# Schematic.net
KiCad netlist of a schematic drawn in EasyEDA
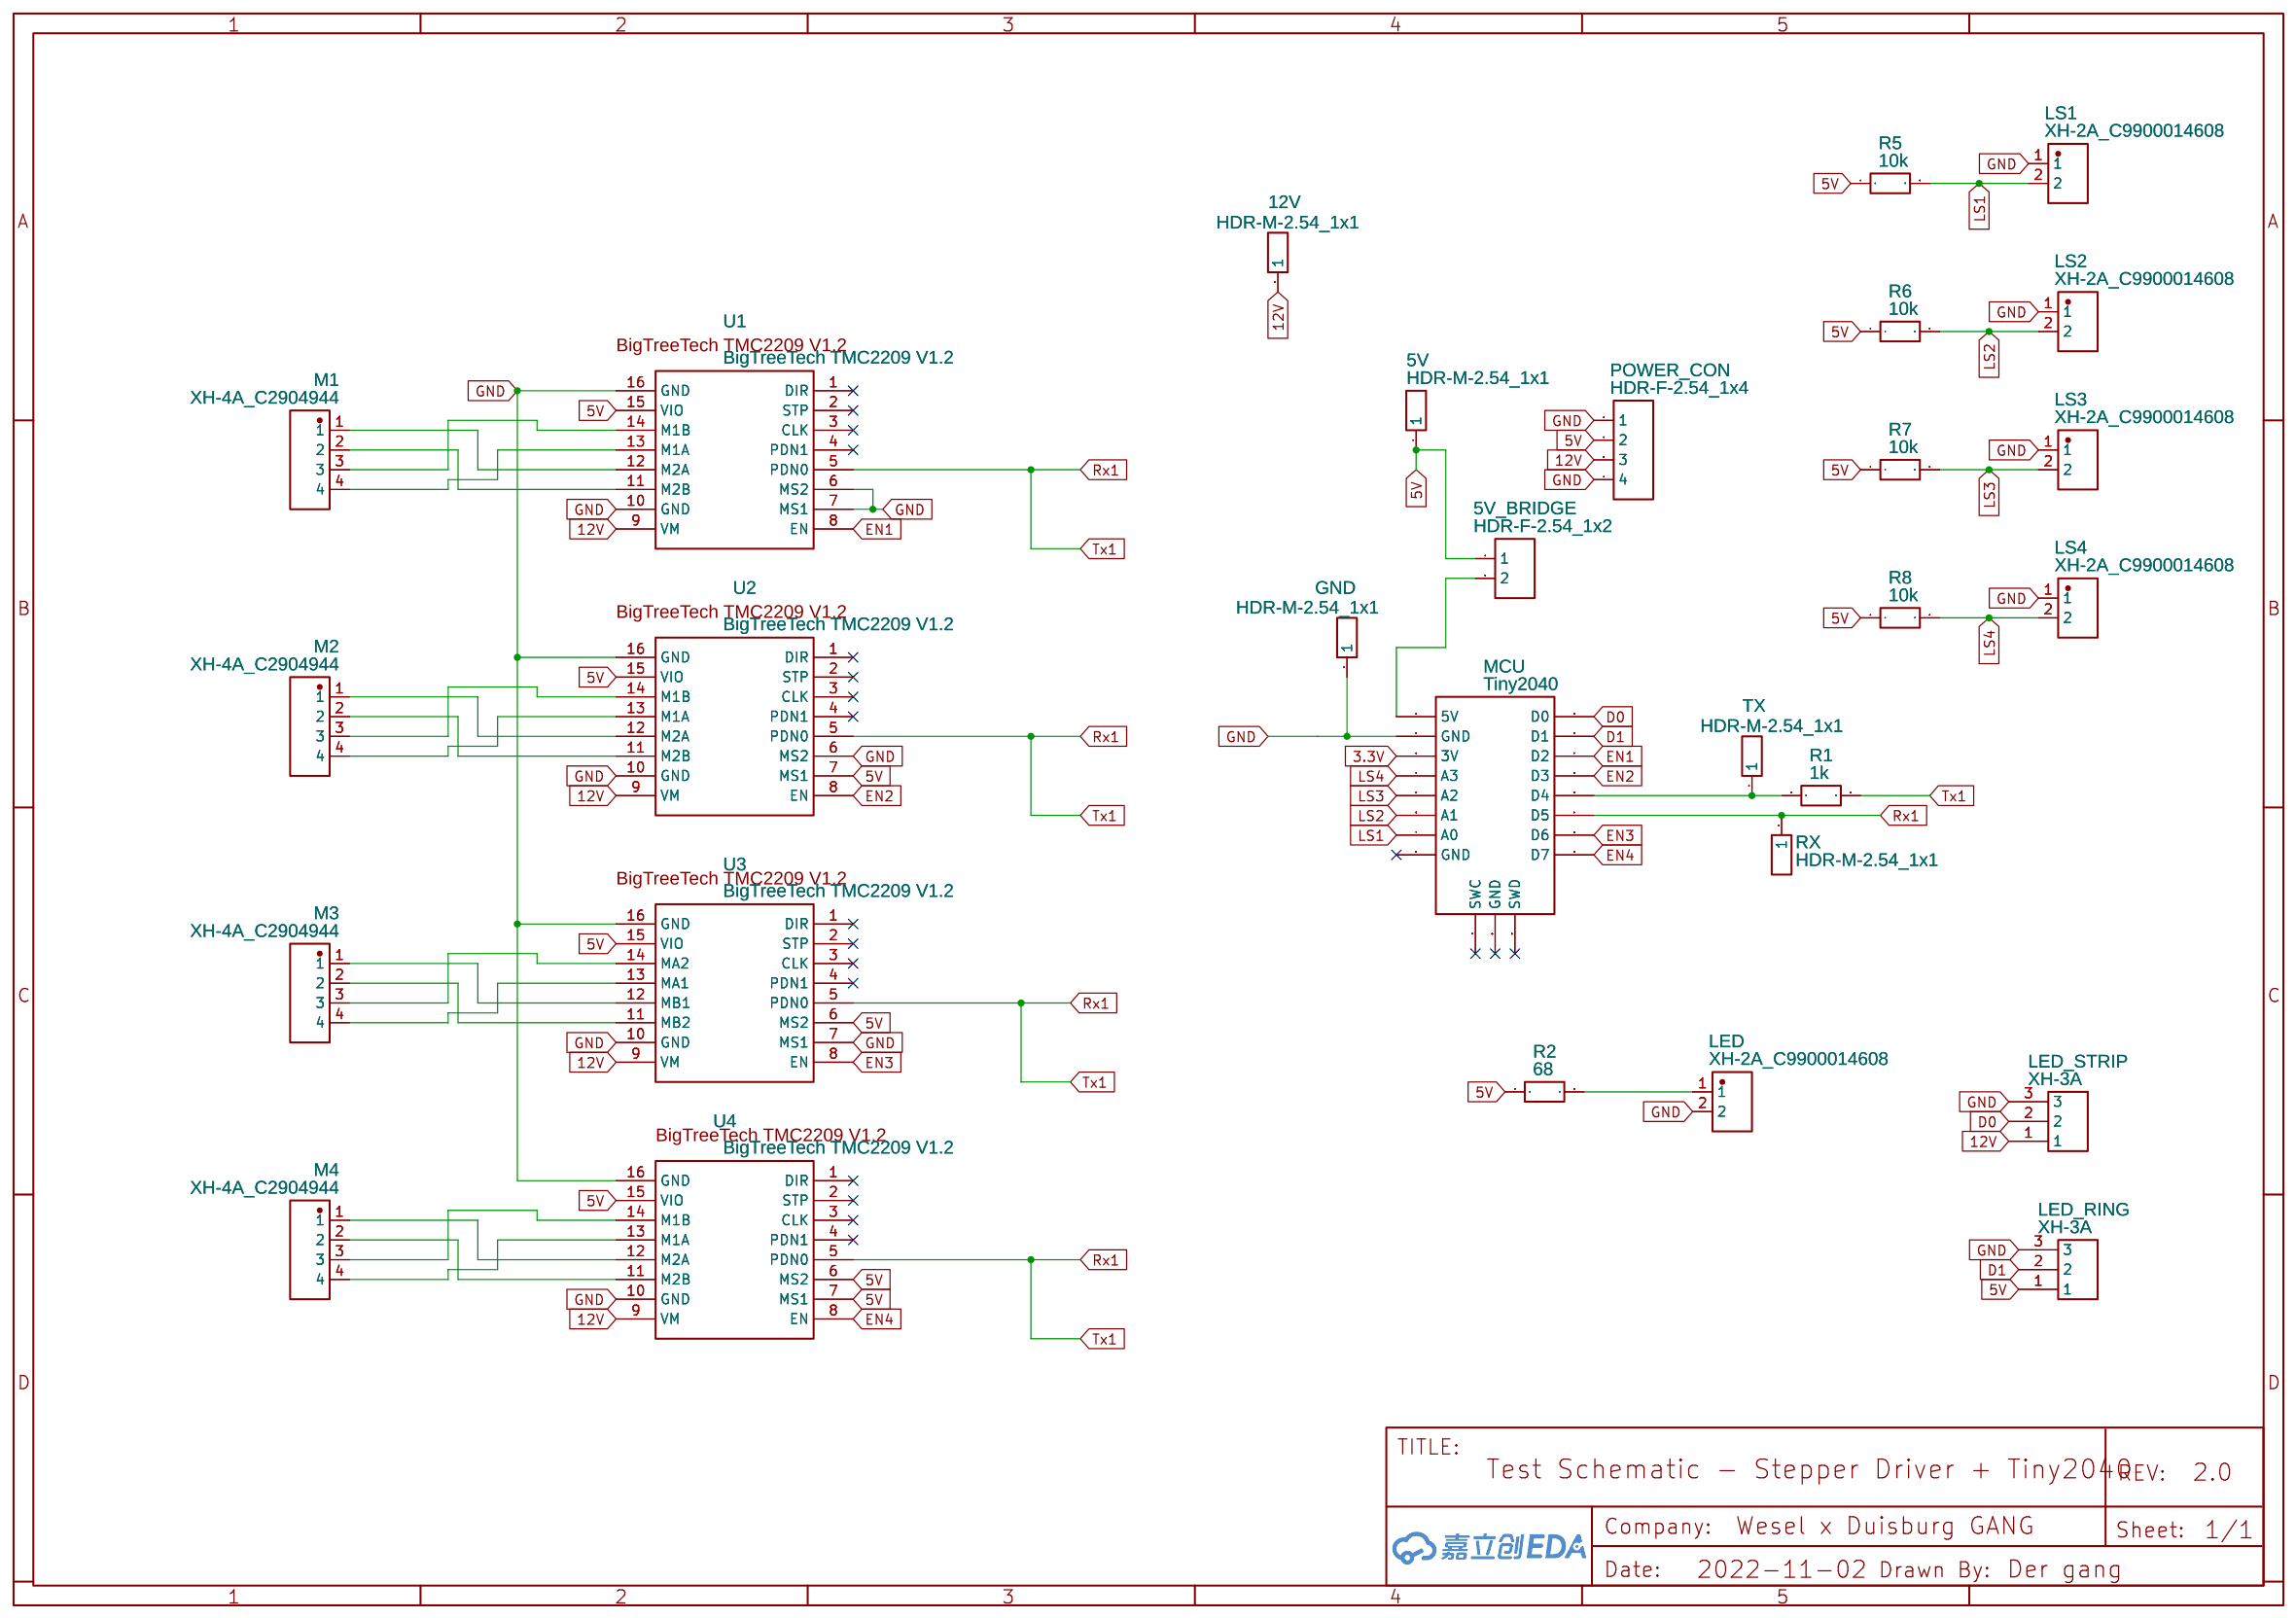
[diagram p0: schematic sheet]

(export (version "E")
  (design (tool "Eeschema 10.0.6"))
  (components
    (comp (ref "5V")
      (value "HDR-M-2.54_1x1")
      (fields (field (name "BOM_Supplier Part") "C81276"))
      (libsource (lib "") (part "HDR-M-2.54_1x1_3"))
    )
    (comp (ref "5V_BRIDGE")
      (value "HDR-F-2.54_1x2")
      (fields (field (name "BOM_Supplier Part") "C49661"))
      (libsource (lib "") (part "HDR-F-2.54_1x2"))
    )
    (comp (ref "12V")
      (value "HDR-M-2.54_1x1")
      (fields (field (name "BOM_Supplier Part") "C81276"))
      (libsource (lib "") (part "HDR-M-2.54_1x1_4"))
    )
    (comp (ref "GND")
      (value "HDR-M-2.54_1x1")
      (fields (field (name "BOM_Supplier Part") "C81276"))
      (libsource (lib "") (part "HDR-M-2.54_1x1"))
    )
    (comp (ref "LED")
      (value "XH-2A_C9900014608")
      (fields (field (name "BOM_Manufacturer Part") "XH-2A") (field (name "BOM_Supplier Part") "C9900014608"))
      (libsource (lib "") (part "XH-2A_C9900014608_1"))
    )
    (comp (ref "LED_RING")
      (value "XH-3A")
      (fields (field (name "BOM_Supplier Part") "C2316"))
      (libsource (lib "") (part "XH-3A"))
    )
    (comp (ref "LED_STRIP")
      (value "XH-3A")
      (fields (field (name "BOM_Supplier Part") "C2316"))
      (libsource (lib "") (part "XH-3A_1"))
    )
    (comp (ref "LS1")
      (value "XH-2A_C9900014608")
      (fields (field (name "BOM_Manufacturer Part") "XH-2A") (field (name "BOM_Supplier Part") "C9900014608"))
      (libsource (lib "") (part "XH-2A_C9900014608"))
    )
    (comp (ref "LS2")
      (value "XH-2A_C9900014608")
      (fields (field (name "BOM_Manufacturer Part") "XH-2A") (field (name "BOM_Supplier Part") "C9900014608"))
      (libsource (lib "") (part "XH-2A_C9900014608"))
    )
    (comp (ref "LS3")
      (value "XH-2A_C9900014608")
      (fields (field (name "BOM_Manufacturer Part") "XH-2A") (field (name "BOM_Supplier Part") "C9900014608"))
      (libsource (lib "") (part "XH-2A_C9900014608"))
    )
    (comp (ref "LS4")
      (value "XH-2A_C9900014608")
      (fields (field (name "BOM_Manufacturer Part") "XH-2A") (field (name "BOM_Supplier Part") "C9900014608"))
      (libsource (lib "") (part "XH-2A_C9900014608"))
    )
    (comp (ref "M1")
      (value "XH-4A_C2904944")
      (fields (field (name "BOM_Manufacturer Part") "XH-4A") (field (name "BOM_Supplier Part") "C2904944"))
      (libsource (lib "") (part "XH-4A_C2904944"))
    )
    (comp (ref "M2")
      (value "XH-4A_C2904944")
      (fields (field (name "BOM_Manufacturer Part") "XH-4A") (field (name "BOM_Supplier Part") "C2904944"))
      (libsource (lib "") (part "XH-4A_C2904944"))
    )
    (comp (ref "M3")
      (value "XH-4A_C2904944")
      (fields (field (name "BOM_Manufacturer Part") "XH-4A") (field (name "BOM_Supplier Part") "C2904944"))
      (libsource (lib "") (part "XH-4A_C2904944"))
    )
    (comp (ref "M4")
      (value "XH-4A_C2904944")
      (fields (field (name "BOM_Manufacturer Part") "XH-4A") (field (name "BOM_Supplier Part") "C2904944"))
      (libsource (lib "") (part "XH-4A_C2904944"))
    )
    (comp (ref "MCU") (value "Tiny2040") (libsource (lib "") (part "Tiny2040")))
    (comp (ref "POWER_CON")
      (value "HDR-F-2.54_1x4")
      (fields (field (name "BOM_Supplier Part") "C225501"))
      (libsource (lib "") (part "HDR-F-2.54_1x4"))
    )
    (comp (ref "R1") (value "1k") (libsource (lib "") (part "R_0603_EU_1")))
    (comp (ref "R2") (value "68") (libsource (lib "") (part "R_AXIAL-0.3_EU")))
    (comp (ref "R5") (value "10k") (libsource (lib "") (part "R_0603_EU")))
    (comp (ref "R6") (value "10k") (libsource (lib "") (part "R_0603_EU")))
    (comp (ref "R7") (value "10k") (libsource (lib "") (part "R_0603_EU")))
    (comp (ref "R8") (value "10k") (libsource (lib "") (part "R_0603_EU")))
    (comp (ref "RX")
      (value "HDR-M-2.54_1x1")
      (fields (field (name "BOM_Supplier Part") "C81276"))
      (libsource (lib "") (part "HDR-M-2.54_1x1_1"))
    )
    (comp (ref "TX")
      (value "HDR-M-2.54_1x1")
      (fields (field (name "BOM_Supplier Part") "C81276"))
      (libsource (lib "") (part "HDR-M-2.54_1x1_2"))
    )
    (comp (ref "U1")
      (value "BigTreeTech TMC2209 V1.2")
      (libsource (lib "") (part "BigTreeTech TMC2209 V1.2_2"))
    )
    (comp (ref "U2")
      (value "BigTreeTech TMC2209 V1.2")
      (libsource (lib "") (part "BigTreeTech TMC2209 V1.2_2"))
    )
    (comp (ref "U3")
      (value "BigTreeTech TMC2209 V1.2")
      (libsource (lib "") (part "BigTreeTech TMC2209 V1.2"))
    )
    (comp (ref "U4")
      (value "BigTreeTech TMC2209 V1.2")
      (libsource (lib "") (part "BigTreeTech TMC2209 V1.2_1"))
    )
  )
  (nets
    (net (code "1") (name "3.3V") (class "Default")
      (node (ref "MCU") (pin "3") (pinfunction "3V_3") (pintype "unspecified"))
    )
    (net (code "2") (name "5V") (class "Default")
      (node (ref "5V") (pin "1") (pinfunction "1_1") (pintype "input"))
      (node (ref "5V_BRIDGE") (pin "1") (pinfunction "1_1") (pintype "input"))
      (node (ref "LED_RING") (pin "1") (pinfunction "1_1") (pintype "unspecified"))
      (node (ref "POWER_CON") (pin "2") (pinfunction "2_2") (pintype "unspecified"))
      (node (ref "R2") (pin "1") (pinfunction "1_1") (pintype "unspecified"))
      (node (ref "R5") (pin "1") (pinfunction "1_1") (pintype "unspecified"))
      (node (ref "R6") (pin "1") (pinfunction "1_1") (pintype "unspecified"))
      (node (ref "R7") (pin "1") (pinfunction "1_1") (pintype "unspecified"))
      (node (ref "R8") (pin "1") (pinfunction "1_1") (pintype "unspecified"))
      (node (ref "U1") (pin "15") (pinfunction "VIO_15") (pintype "unspecified"))
      (node (ref "U2") (pin "15") (pinfunction "VIO_15") (pintype "unspecified"))
      (node (ref "U2") (pin "7") (pinfunction "MS1_7") (pintype "unspecified"))
      (node (ref "U3") (pin "15") (pinfunction "VIO_15") (pintype "unspecified"))
      (node (ref "U3") (pin "6") (pinfunction "MS2_6") (pintype "unspecified"))
      (node (ref "U4") (pin "15") (pinfunction "VIO_15") (pintype "unspecified"))
      (node (ref "U4") (pin "6") (pinfunction "MS2_6") (pintype "unspecified"))
      (node (ref "U4") (pin "7") (pinfunction "MS1_7") (pintype "unspecified"))
    )
    (net (code "3") (name "12V") (class "Default")
      (node (ref "12V") (pin "1") (pinfunction "1_1") (pintype "input"))
      (node (ref "LED_STRIP") (pin "1") (pinfunction "1_1") (pintype "unspecified"))
      (node (ref "POWER_CON") (pin "3") (pinfunction "3_3") (pintype "unspecified"))
      (node (ref "U1") (pin "9") (pinfunction "VM_9") (pintype "unspecified"))
      (node (ref "U2") (pin "9") (pinfunction "VM_9") (pintype "unspecified"))
      (node (ref "U3") (pin "9") (pinfunction "VM_9") (pintype "unspecified"))
      (node (ref "U4") (pin "9") (pinfunction "VM_9") (pintype "unspecified"))
    )
    (net (code "4") (name "D0") (class "Default")
      (node (ref "LED_STRIP") (pin "2") (pinfunction "2_2") (pintype "unspecified"))
      (node (ref "MCU") (pin "19") (pinfunction "D0_19") (pintype "unspecified"))
    )
    (net (code "5") (name "D1") (class "Default")
      (node (ref "LED_RING") (pin "2") (pinfunction "2_2") (pintype "unspecified"))
      (node (ref "MCU") (pin "18") (pinfunction "D1_18") (pintype "unspecified"))
    )
    (net (code "6") (name "EN1") (class "Default")
      (node (ref "MCU") (pin "17") (pinfunction "D2_17") (pintype "unspecified"))
      (node (ref "U1") (pin "8") (pinfunction "EN_8") (pintype "unspecified"))
    )
    (net (code "7") (name "EN2") (class "Default")
      (node (ref "MCU") (pin "16") (pinfunction "D3_16") (pintype "unspecified"))
      (node (ref "U2") (pin "8") (pinfunction "EN_8") (pintype "unspecified"))
    )
    (net (code "8") (name "EN3") (class "Default")
      (node (ref "MCU") (pin "13") (pinfunction "D6_13") (pintype "unspecified"))
      (node (ref "U3") (pin "8") (pinfunction "EN_8") (pintype "unspecified"))
    )
    (net (code "9") (name "EN4") (class "Default")
      (node (ref "MCU") (pin "12") (pinfunction "D7_12") (pintype "unspecified"))
      (node (ref "U4") (pin "8") (pinfunction "EN_8") (pintype "unspecified"))
    )
    (net (code "10") (name "GND") (class "Default")
      (node (ref "GND") (pin "1") (pinfunction "1_1") (pintype "input"))
      (node (ref "LED") (pin "2") (pinfunction "2_2") (pintype "unspecified"))
      (node (ref "LED_RING") (pin "3") (pinfunction "3_3") (pintype "unspecified"))
      (node (ref "LED_STRIP") (pin "3") (pinfunction "3_3") (pintype "unspecified"))
      (node (ref "LS1") (pin "1") (pinfunction "1_1") (pintype "unspecified"))
      (node (ref "LS2") (pin "1") (pinfunction "1_1") (pintype "unspecified"))
      (node (ref "LS3") (pin "1") (pinfunction "1_1") (pintype "unspecified"))
      (node (ref "LS4") (pin "1") (pinfunction "1_1") (pintype "unspecified"))
      (node (ref "MCU") (pin "2") (pinfunction "GND_2") (pintype "unspecified"))
      (node (ref "POWER_CON") (pin "1") (pinfunction "1_1") (pintype "unspecified"))
      (node (ref "POWER_CON") (pin "4") (pinfunction "4_4") (pintype "unspecified"))
      (node (ref "U1") (pin "10") (pinfunction "GND_10") (pintype "unspecified"))
      (node (ref "U1") (pin "16") (pinfunction "GND_16") (pintype "unspecified"))
      (node (ref "U1") (pin "6") (pinfunction "MS2_6") (pintype "unspecified"))
      (node (ref "U1") (pin "7") (pinfunction "MS1_7") (pintype "unspecified"))
      (node (ref "U2") (pin "10") (pinfunction "GND_10") (pintype "unspecified"))
      (node (ref "U2") (pin "16") (pinfunction "GND_16") (pintype "unspecified"))
      (node (ref "U2") (pin "6") (pinfunction "MS2_6") (pintype "unspecified"))
      (node (ref "U3") (pin "10") (pinfunction "GND_10") (pintype "unspecified"))
      (node (ref "U3") (pin "16") (pinfunction "GND_16") (pintype "unspecified"))
      (node (ref "U3") (pin "7") (pinfunction "MS1_7") (pintype "unspecified"))
      (node (ref "U4") (pin "10") (pinfunction "GND_10") (pintype "unspecified"))
      (node (ref "U4") (pin "16") (pinfunction "GND_16") (pintype "unspecified"))
    )
    (net (code "11") (name "LS1") (class "Default")
      (node (ref "LS1") (pin "2") (pinfunction "2_2") (pintype "unspecified"))
      (node (ref "MCU") (pin "7") (pinfunction "A0_7") (pintype "unspecified"))
      (node (ref "R5") (pin "2") (pinfunction "2_2") (pintype "unspecified"))
    )
    (net (code "12") (name "LS2") (class "Default")
      (node (ref "LS2") (pin "2") (pinfunction "2_2") (pintype "unspecified"))
      (node (ref "MCU") (pin "6") (pinfunction "A1_6") (pintype "unspecified"))
      (node (ref "R6") (pin "2") (pinfunction "2_2") (pintype "unspecified"))
    )
    (net (code "13") (name "LS3") (class "Default")
      (node (ref "LS3") (pin "2") (pinfunction "2_2") (pintype "unspecified"))
      (node (ref "MCU") (pin "5") (pinfunction "A2_5") (pintype "unspecified"))
      (node (ref "R7") (pin "2") (pinfunction "2_2") (pintype "unspecified"))
    )
    (net (code "14") (name "LS4") (class "Default")
      (node (ref "LS4") (pin "2") (pinfunction "2_2") (pintype "unspecified"))
      (node (ref "MCU") (pin "4") (pinfunction "A3_4") (pintype "unspecified"))
      (node (ref "R8") (pin "2") (pinfunction "2_2") (pintype "unspecified"))
    )
    (net (code "15") (name "Net-(LED-Pad1)") (class "Default")
      (node (ref "LED") (pin "1") (pinfunction "1_1") (pintype "unspecified"))
      (node (ref "R2") (pin "2") (pinfunction "2_2") (pintype "unspecified"))
    )
    (net (code "16") (name "Net-(MCU-5V)") (class "Default")
      (node (ref "5V_BRIDGE") (pin "2") (pinfunction "2_2") (pintype "input"))
      (node (ref "MCU") (pin "1") (pinfunction "5V_1") (pintype "unspecified"))
    )
    (net (code "17") (name "Net-(MCU-D4)") (class "Default")
      (node (ref "MCU") (pin "15") (pinfunction "D4_15") (pintype "unspecified"))
      (node (ref "R1") (pin "2") (pinfunction "2_2") (pintype "unspecified"))
      (node (ref "TX") (pin "1") (pinfunction "1_1") (pintype "input"))
    )
    (net (code "18") (name "Net-(U1-M1A)") (class "Default")
      (node (ref "M1") (pin "4") (pinfunction "4_4") (pintype "unspecified"))
      (node (ref "U1") (pin "13") (pinfunction "M1A_13") (pintype "unspecified"))
    )
    (net (code "19") (name "Net-(U1-M1B)") (class "Default")
      (node (ref "M1") (pin "3") (pinfunction "3_3") (pintype "unspecified"))
      (node (ref "U1") (pin "14") (pinfunction "M1B_14") (pintype "unspecified"))
    )
    (net (code "20") (name "Net-(U1-M2A)") (class "Default")
      (node (ref "M1") (pin "1") (pinfunction "1_1") (pintype "unspecified"))
      (node (ref "U1") (pin "12") (pinfunction "M2A_12") (pintype "unspecified"))
    )
    (net (code "21") (name "Net-(U1-M2B)") (class "Default")
      (node (ref "M1") (pin "2") (pinfunction "2_2") (pintype "unspecified"))
      (node (ref "U1") (pin "11") (pinfunction "M2B_11") (pintype "unspecified"))
    )
    (net (code "22") (name "Net-(U2-M1A)") (class "Default")
      (node (ref "M2") (pin "4") (pinfunction "4_4") (pintype "unspecified"))
      (node (ref "U2") (pin "13") (pinfunction "M1A_13") (pintype "unspecified"))
    )
    (net (code "23") (name "Net-(U2-M1B)") (class "Default")
      (node (ref "M2") (pin "3") (pinfunction "3_3") (pintype "unspecified"))
      (node (ref "U2") (pin "14") (pinfunction "M1B_14") (pintype "unspecified"))
    )
    (net (code "24") (name "Net-(U2-M2A)") (class "Default")
      (node (ref "M2") (pin "1") (pinfunction "1_1") (pintype "unspecified"))
      (node (ref "U2") (pin "12") (pinfunction "M2A_12") (pintype "unspecified"))
    )
    (net (code "25") (name "Net-(U2-M2B)") (class "Default")
      (node (ref "M2") (pin "2") (pinfunction "2_2") (pintype "unspecified"))
      (node (ref "U2") (pin "11") (pinfunction "M2B_11") (pintype "unspecified"))
    )
    (net (code "26") (name "Net-(U3-MA1)") (class "Default")
      (node (ref "M3") (pin "4") (pinfunction "4_4") (pintype "unspecified"))
      (node (ref "U3") (pin "13") (pinfunction "MA1_13") (pintype "unspecified"))
    )
    (net (code "27") (name "Net-(U3-MA2)") (class "Default")
      (node (ref "M3") (pin "3") (pinfunction "3_3") (pintype "unspecified"))
      (node (ref "U3") (pin "14") (pinfunction "MA2_14") (pintype "unspecified"))
    )
    (net (code "28") (name "Net-(U3-MB1)") (class "Default")
      (node (ref "M3") (pin "1") (pinfunction "1_1") (pintype "unspecified"))
      (node (ref "U3") (pin "12") (pinfunction "MB1_12") (pintype "unspecified"))
    )
    (net (code "29") (name "Net-(U3-MB2)") (class "Default")
      (node (ref "M3") (pin "2") (pinfunction "2_2") (pintype "unspecified"))
      (node (ref "U3") (pin "11") (pinfunction "MB2_11") (pintype "unspecified"))
    )
    (net (code "30") (name "Net-(U4-M1A)") (class "Default")
      (node (ref "M4") (pin "4") (pinfunction "4_4") (pintype "unspecified"))
      (node (ref "U4") (pin "13") (pinfunction "M1A_13") (pintype "unspecified"))
    )
    (net (code "31") (name "Net-(U4-M1B)") (class "Default")
      (node (ref "M4") (pin "3") (pinfunction "3_3") (pintype "unspecified"))
      (node (ref "U4") (pin "14") (pinfunction "M1B_14") (pintype "unspecified"))
    )
    (net (code "32") (name "Net-(U4-M2A)") (class "Default")
      (node (ref "M4") (pin "1") (pinfunction "1_1") (pintype "unspecified"))
      (node (ref "U4") (pin "12") (pinfunction "M2A_12") (pintype "unspecified"))
    )
    (net (code "33") (name "Net-(U4-M2B)") (class "Default")
      (node (ref "M4") (pin "2") (pinfunction "2_2") (pintype "unspecified"))
      (node (ref "U4") (pin "11") (pinfunction "M2B_11") (pintype "unspecified"))
    )
    (net (code "34") (name "Rx1") (class "Default")
      (node (ref "MCU") (pin "14") (pinfunction "D5_14") (pintype "unspecified"))
      (node (ref "R1") (pin "1") (pinfunction "1_1") (pintype "unspecified"))
      (node (ref "RX") (pin "1") (pinfunction "1_1") (pintype "input"))
      (node (ref "U1") (pin "5") (pinfunction "PDN0_5") (pintype "unspecified"))
      (node (ref "U2") (pin "5") (pinfunction "PDN0_5") (pintype "unspecified"))
      (node (ref "U3") (pin "5") (pinfunction "PDN0_5") (pintype "unspecified"))
      (node (ref "U4") (pin "5") (pinfunction "PDN0_5") (pintype "unspecified"))
    )
    (net (code "35") (name "unconnected-(MCU-GND-Pad8)") (class "Default")
      (node (ref "MCU") (pin "8") (pinfunction "GND_8") (pintype "unspecified+no_connect"))
    )
    (net (code "36") (name "unconnected-(MCU-GND-Pad10)") (class "Default")
      (node (ref "MCU") (pin "10") (pinfunction "GND_10") (pintype "unspecified+no_connect"))
    )
    (net (code "37") (name "unconnected-(MCU-SWC-Pad9)") (class "Default")
      (node (ref "MCU") (pin "9") (pinfunction "SWC_9") (pintype "unspecified+no_connect"))
    )
    (net (code "38") (name "unconnected-(MCU-SWD-Pad11)") (class "Default")
      (node (ref "MCU") (pin "11") (pinfunction "SWD_11") (pintype "unspecified+no_connect"))
    )
    (net (code "39") (name "unconnected-(U1-CLK-Pad3)") (class "Default")
      (node (ref "U1") (pin "3") (pinfunction "CLK_3") (pintype "unspecified+no_connect"))
    )
    (net (code "40") (name "unconnected-(U1-DIR-Pad1)") (class "Default")
      (node (ref "U1") (pin "1") (pinfunction "DIR_1") (pintype "unspecified+no_connect"))
    )
    (net (code "41") (name "unconnected-(U1-PDN1-Pad4)") (class "Default")
      (node (ref "U1") (pin "4") (pinfunction "PDN1_4") (pintype "unspecified+no_connect"))
    )
    (net (code "42") (name "unconnected-(U1-STP-Pad2)") (class "Default")
      (node (ref "U1") (pin "2") (pinfunction "STP_2") (pintype "unspecified+no_connect"))
    )
    (net (code "43") (name "unconnected-(U2-CLK-Pad3)") (class "Default")
      (node (ref "U2") (pin "3") (pinfunction "CLK_3") (pintype "unspecified+no_connect"))
    )
    (net (code "44") (name "unconnected-(U2-DIR-Pad1)") (class "Default")
      (node (ref "U2") (pin "1") (pinfunction "DIR_1") (pintype "unspecified+no_connect"))
    )
    (net (code "45") (name "unconnected-(U2-PDN1-Pad4)") (class "Default")
      (node (ref "U2") (pin "4") (pinfunction "PDN1_4") (pintype "unspecified+no_connect"))
    )
    (net (code "46") (name "unconnected-(U2-STP-Pad2)") (class "Default")
      (node (ref "U2") (pin "2") (pinfunction "STP_2") (pintype "unspecified+no_connect"))
    )
    (net (code "47") (name "unconnected-(U3-CLK-Pad3)") (class "Default")
      (node (ref "U3") (pin "3") (pinfunction "CLK_3") (pintype "unspecified+no_connect"))
    )
    (net (code "48") (name "unconnected-(U3-DIR-Pad1)") (class "Default")
      (node (ref "U3") (pin "1") (pinfunction "DIR_1") (pintype "unspecified+no_connect"))
    )
    (net (code "49") (name "unconnected-(U3-PDN1-Pad4)") (class "Default")
      (node (ref "U3") (pin "4") (pinfunction "PDN1_4") (pintype "unspecified+no_connect"))
    )
    (net (code "50") (name "unconnected-(U3-STP-Pad2)") (class "Default")
      (node (ref "U3") (pin "2") (pinfunction "STP_2") (pintype "unspecified+no_connect"))
    )
    (net (code "51") (name "unconnected-(U4-CLK-Pad3)") (class "Default")
      (node (ref "U4") (pin "3") (pinfunction "CLK_3") (pintype "unspecified+no_connect"))
    )
    (net (code "52") (name "unconnected-(U4-DIR-Pad1)") (class "Default")
      (node (ref "U4") (pin "1") (pinfunction "DIR_1") (pintype "unspecified+no_connect"))
    )
    (net (code "53") (name "unconnected-(U4-PDN1-Pad4)") (class "Default")
      (node (ref "U4") (pin "4") (pinfunction "PDN1_4") (pintype "unspecified+no_connect"))
    )
    (net (code "54") (name "unconnected-(U4-STP-Pad2)") (class "Default")
      (node (ref "U4") (pin "2") (pinfunction "STP_2") (pintype "unspecified+no_connect"))
    )
  )
)
